# Etage0_ok_2.net
KiCad netlist of a schematic drawn in EAGLE
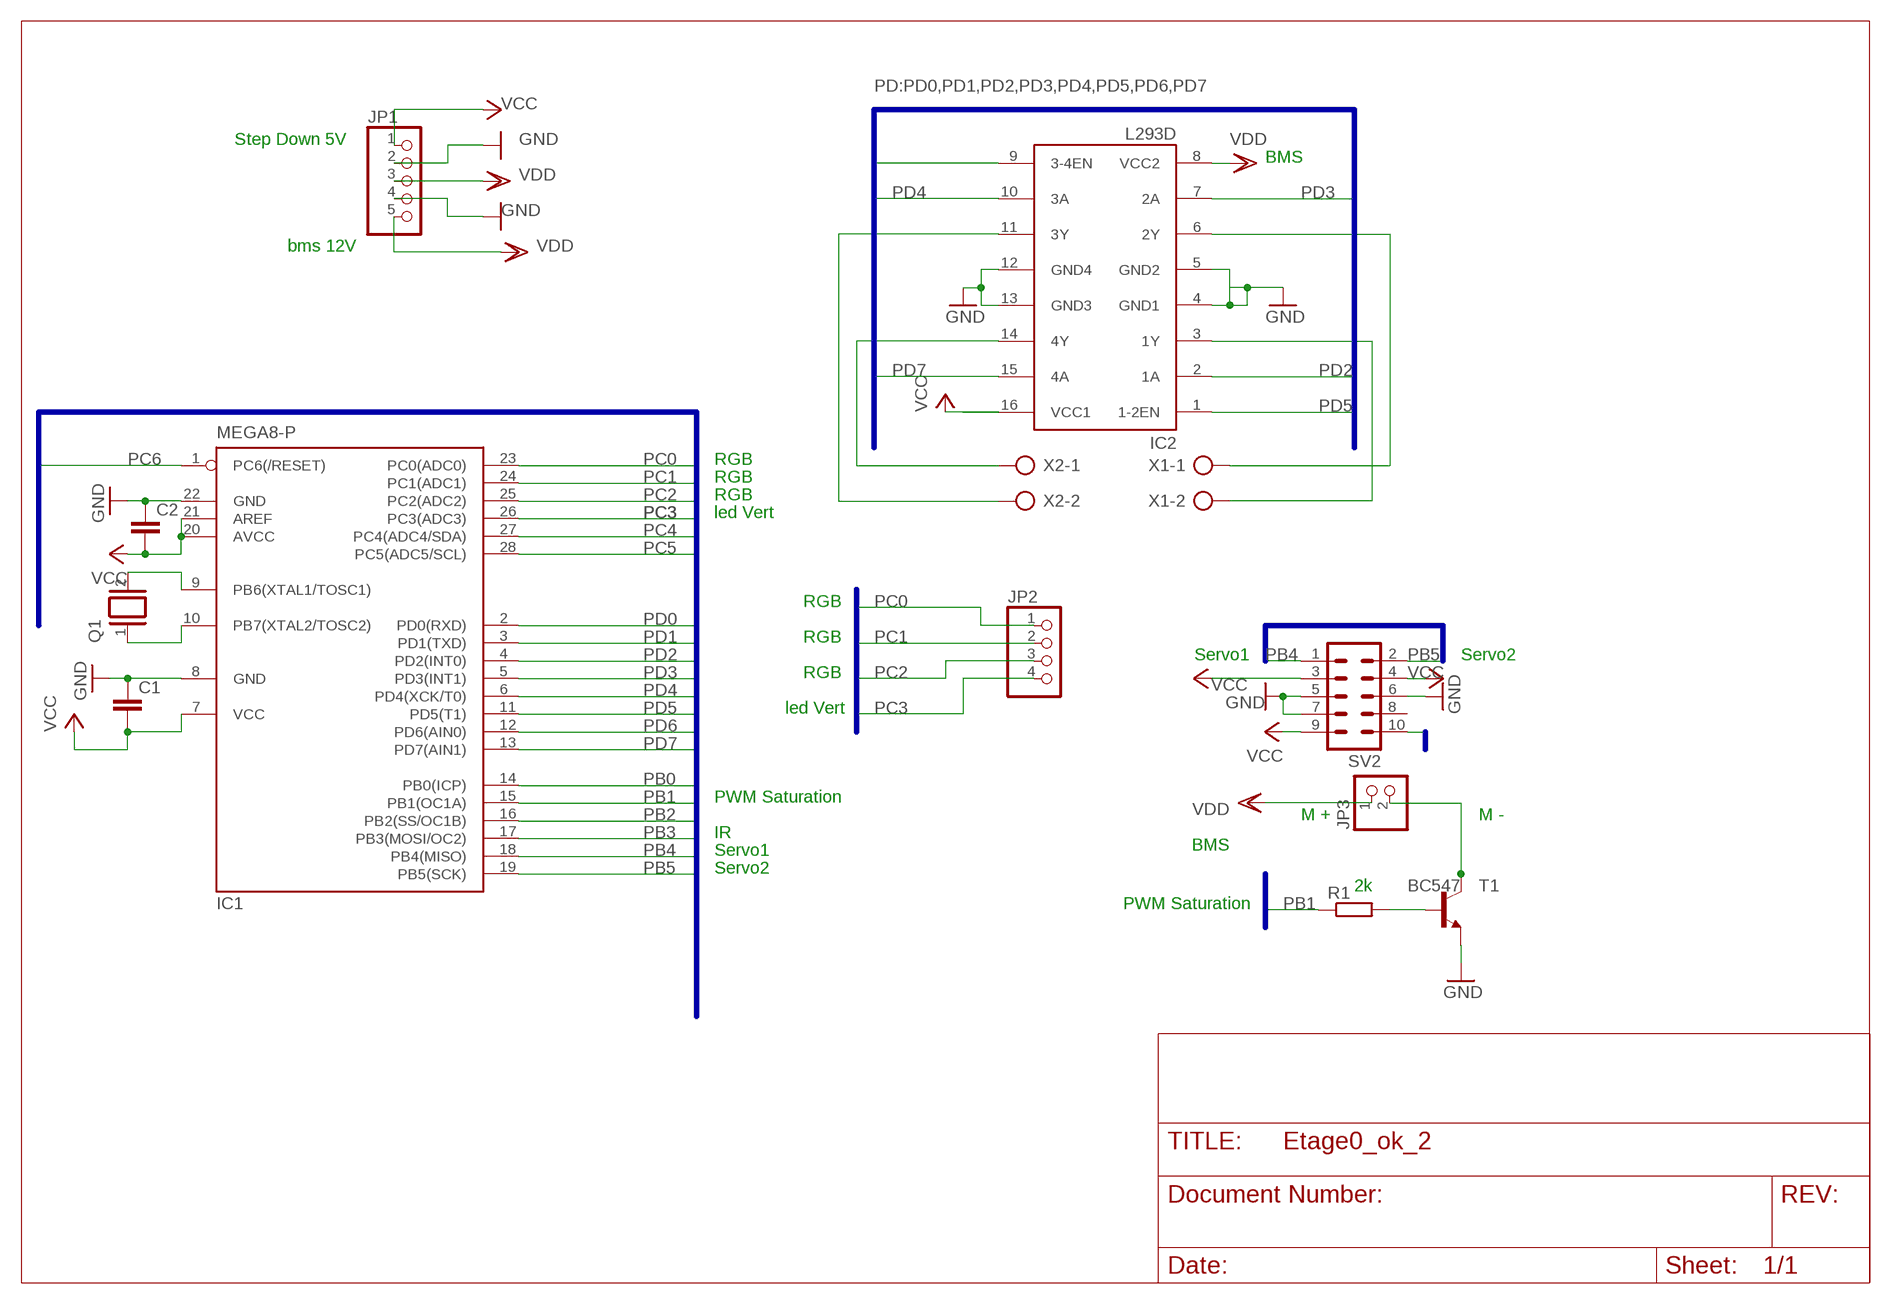
[diagram p0: schematic, sheet 1]

(export (version "E")
  (design (tool "Eeschema 10.0.6"))
  (components
    (comp (ref "C1")
      (value "C-EUC1206")
      (footprint "eagle-import:C1206")
      (libsource (lib "eagle-import") (part "C-EUC1206"))
    )
    (comp (ref "C2")
      (value "C-EUC1206")
      (footprint "eagle-import:C1206")
      (libsource (lib "eagle-import") (part "C-EUC1206"))
    )
    (comp (ref "IC1")
      (value "MEGA8-P")
      (footprint "eagle-import:DIL28-3")
      (libsource (lib "eagle-import") (part "MEGA8-P"))
    )
    (comp (ref "IC2")
      (value "L293D")
      (footprint "eagle-import:DIL16")
      (libsource (lib "eagle-import") (part "L293D"))
    )
    (comp (ref "JP1")
      (value "PINHD-1X5")
      (footprint "eagle-import:1X05")
      (libsource (lib "eagle-import") (part "PINHD-1X5"))
    )
    (comp (ref "JP2")
      (value "PINHD-1X4")
      (footprint "eagle-import:1X04")
      (libsource (lib "eagle-import") (part "PINHD-1X4"))
    )
    (comp (ref "JP3")
      (value "PINHD-1X2")
      (footprint "eagle-import:1X02")
      (libsource (lib "eagle-import") (part "PINHD-1X2"))
    )
    (comp (ref "Q1")
      (value "XTAL")
      (footprint "eagle-import:Q")
      (libsource (lib "eagle-import") (part "XTAL"))
    )
    (comp (ref "R1")
      (value "R-EU_0204/7")
      (footprint "eagle-import:0204_7")
      (libsource (lib "eagle-import") (part "R-EU_0204/7"))
    )
    (comp (ref "SV2")
      (value "MA05-2")
      (footprint "eagle-import:MA05-2")
      (libsource (lib "eagle-import") (part "MA05-2"))
    )
    (comp (ref "T1")
      (value "BC547")
      (footprint "eagle-import:TO92")
      (libsource (lib "eagle-import") (part "BC547"))
    )
    (comp (ref "X1")
      (value "AK300/2")
      (footprint "eagle-import:AK300_2")
      (libsource (lib "eagle-import") (part "AK300/2"))
    )
    (comp (ref "X2")
      (value "AK300/2")
      (footprint "eagle-import:AK300_2")
      (libsource (lib "eagle-import") (part "AK300/2"))
    )
  )
  (nets
    (net (code "2") (name "/PB0") (class "Default")
      (node (ref "IC1") (pin "14") (pinfunction "PB0(ICP)_14") (pintype "bidirectional"))
    )
    (net (code "3") (name "/PB1") (class "Default")
      (node (ref "IC1") (pin "15") (pinfunction "PB1(OC1A)_15") (pintype "bidirectional"))
      (node (ref "R1") (pin "1") (pinfunction "1_1") (pintype "passive"))
    )
    (net (code "4") (name "/PB2") (class "Default")
      (node (ref "IC1") (pin "16") (pinfunction "PB2(SS/OC1B)_16") (pintype "bidirectional"))
    )
    (net (code "5") (name "/PB3") (class "Default")
      (node (ref "IC1") (pin "17") (pinfunction "PB3(MOSI/OC2)_17") (pintype "bidirectional"))
      (node (ref "SV2") (pin "10") (pinfunction "10_10") (pintype "passive"))
    )
    (net (code "6") (name "/PB4") (class "Default")
      (node (ref "IC1") (pin "18") (pinfunction "PB4(MISO)_18") (pintype "bidirectional"))
      (node (ref "SV2") (pin "1") (pinfunction "1_1") (pintype "passive"))
    )
    (net (code "7") (name "/PB5") (class "Default")
      (node (ref "IC1") (pin "19") (pinfunction "PB5(SCK)_19") (pintype "bidirectional"))
      (node (ref "SV2") (pin "2") (pinfunction "2_2") (pintype "passive"))
    )
    (net (code "8") (name "/PC0") (class "Default")
      (node (ref "IC1") (pin "23") (pinfunction "PC0(ADC0)_23") (pintype "bidirectional"))
      (node (ref "JP2") (pin "1") (pinfunction "1_1") (pintype "passive"))
    )
    (net (code "9") (name "/PC1") (class "Default")
      (node (ref "IC1") (pin "24") (pinfunction "PC1(ADC1)_24") (pintype "bidirectional"))
      (node (ref "JP2") (pin "2") (pinfunction "2_2") (pintype "passive"))
    )
    (net (code "10") (name "/PC2") (class "Default")
      (node (ref "IC1") (pin "25") (pinfunction "PC2(ADC2)_25") (pintype "bidirectional"))
      (node (ref "JP2") (pin "3") (pinfunction "3_3") (pintype "passive"))
    )
    (net (code "11") (name "/PC3") (class "Default")
      (node (ref "IC1") (pin "26") (pinfunction "PC3(ADC3)_26") (pintype "bidirectional"))
      (node (ref "JP2") (pin "4") (pinfunction "4_4") (pintype "passive"))
    )
    (net (code "12") (name "/PC4") (class "Default")
      (node (ref "IC1") (pin "27") (pinfunction "PC4(ADC4/SDA)_27") (pintype "bidirectional"))
    )
    (net (code "13") (name "/PC5") (class "Default")
      (node (ref "IC1") (pin "28") (pinfunction "PC5(ADC5/SCL)_28") (pintype "bidirectional"))
    )
    (net (code "14") (name "/PC6") (class "Default")
      (node (ref "IC1") (pin "1") (pinfunction "PC6(/RESET)_1") (pintype "bidirectional"))
    )
    (net (code "15") (name "/PD0") (class "Default")
      (node (ref "IC1") (pin "2") (pinfunction "PD0(RXD)_2") (pintype "bidirectional"))
    )
    (net (code "16") (name "/PD1") (class "Default")
      (node (ref "IC1") (pin "3") (pinfunction "PD1(TXD)_3") (pintype "bidirectional"))
    )
    (net (code "17") (name "/PD2") (class "Default")
      (node (ref "IC1") (pin "4") (pinfunction "PD2(INT0)_4") (pintype "bidirectional"))
      (node (ref "IC2") (pin "2") (pinfunction "1A_2") (pintype "input"))
    )
    (net (code "18") (name "/PD3") (class "Default")
      (node (ref "IC1") (pin "5") (pinfunction "PD3(INT1)_5") (pintype "bidirectional"))
      (node (ref "IC2") (pin "7") (pinfunction "2A_7") (pintype "input"))
    )
    (net (code "19") (name "/PD4") (class "Default")
      (node (ref "IC1") (pin "6") (pinfunction "PD4(XCK/T0)_6") (pintype "bidirectional"))
      (node (ref "IC2") (pin "10") (pinfunction "3A_10") (pintype "input"))
    )
    (net (code "20") (name "/PD5") (class "Default")
      (node (ref "IC1") (pin "11") (pinfunction "PD5(T1)_11") (pintype "bidirectional"))
      (node (ref "IC2") (pin "1") (pinfunction "1-2EN_1") (pintype "input"))
    )
    (net (code "21") (name "/PD6") (class "Default")
      (node (ref "IC1") (pin "12") (pinfunction "PD6(AIN0)_12") (pintype "bidirectional"))
      (node (ref "IC2") (pin "9") (pinfunction "3-4EN_9") (pintype "input"))
    )
    (net (code "22") (name "/PD7") (class "Default")
      (node (ref "IC1") (pin "13") (pinfunction "PD7(AIN1)_13") (pintype "bidirectional"))
      (node (ref "IC2") (pin "15") (pinfunction "4A_15") (pintype "input"))
    )
    (net (code "24") (name "GND") (class "Default")
      (node (ref "C1") (pin "1") (pinfunction "1_1") (pintype "passive"))
      (node (ref "C2") (pin "1") (pinfunction "1_1") (pintype "passive"))
      (node (ref "IC1") (pin "22") (pinfunction "GND_22") (pintype "power_in"))
      (node (ref "IC1") (pin "8") (pinfunction "GND_8") (pintype "power_in"))
      (node (ref "IC2") (pin "12") (pinfunction "GND4_12") (pintype "power_in"))
      (node (ref "IC2") (pin "13") (pinfunction "GND3_13") (pintype "power_in"))
      (node (ref "IC2") (pin "4") (pinfunction "GND1_4") (pintype "power_in"))
      (node (ref "IC2") (pin "5") (pinfunction "GND2_5") (pintype "power_in"))
      (node (ref "JP1") (pin "2") (pinfunction "2_2") (pintype "passive"))
      (node (ref "JP1") (pin "4") (pinfunction "4_4") (pintype "passive"))
      (node (ref "SV2") (pin "5") (pinfunction "5_5") (pintype "passive"))
      (node (ref "SV2") (pin "6") (pinfunction "6_6") (pintype "passive"))
      (node (ref "SV2") (pin "7") (pinfunction "7_7") (pintype "passive"))
      (node (ref "T1") (pin "1") (pinfunction "E_1") (pintype "passive"))
    )
    (net (code "25") (name "Net-(IC1-PB6(XTAL1{slash}TOSC1))") (class "Default")
      (node (ref "IC1") (pin "9") (pinfunction "PB6(XTAL1/TOSC1)_9") (pintype "bidirectional"))
      (node (ref "Q1") (pin "2") (pinfunction "2_2") (pintype "passive"))
    )
    (net (code "26") (name "Net-(IC1-PB7(XTAL2{slash}TOSC2))") (class "Default")
      (node (ref "IC1") (pin "10") (pinfunction "PB7(XTAL2/TOSC2)_10") (pintype "bidirectional"))
      (node (ref "Q1") (pin "1") (pinfunction "1_1") (pintype "passive"))
    )
    (net (code "27") (name "Net-(IC2-1Y)") (class "Default")
      (node (ref "IC2") (pin "3") (pinfunction "1Y_3") (pintype "output"))
      (node (ref "X1") (pin "2") (pinfunction "KL_2") (pintype "passive"))
    )
    (net (code "28") (name "Net-(IC2-2Y)") (class "Default")
      (node (ref "IC2") (pin "6") (pinfunction "2Y_6") (pintype "output"))
      (node (ref "X1") (pin "1") (pinfunction "KL_1") (pintype "passive"))
    )
    (net (code "29") (name "Net-(IC2-3Y)") (class "Default")
      (node (ref "IC2") (pin "11") (pinfunction "3Y_11") (pintype "output"))
      (node (ref "X2") (pin "2") (pinfunction "KL_2") (pintype "passive"))
    )
    (net (code "30") (name "Net-(IC2-4Y)") (class "Default")
      (node (ref "IC2") (pin "14") (pinfunction "4Y_14") (pintype "output"))
      (node (ref "X2") (pin "1") (pinfunction "KL_1") (pintype "passive"))
    )
    (net (code "31") (name "Net-(T1-B)") (class "Default")
      (node (ref "R1") (pin "2") (pinfunction "2_2") (pintype "passive"))
      (node (ref "T1") (pin "2") (pinfunction "B_2") (pintype "passive"))
    )
    (net (code "32") (name "Net-(T1-C)") (class "Default")
      (node (ref "JP3") (pin "2") (pinfunction "2_2") (pintype "passive"))
      (node (ref "T1") (pin "3") (pinfunction "C_3") (pintype "passive"))
    )
    (net (code "33") (name "VCC") (class "Default")
      (node (ref "C1") (pin "2") (pinfunction "2_2") (pintype "passive"))
      (node (ref "C2") (pin "2") (pinfunction "2_2") (pintype "passive"))
      (node (ref "IC1") (pin "20") (pinfunction "AVCC_20") (pintype "power_in"))
      (node (ref "IC1") (pin "21") (pinfunction "AREF_21") (pintype "passive"))
      (node (ref "IC1") (pin "7") (pinfunction "VCC_7") (pintype "power_in"))
      (node (ref "IC2") (pin "16") (pinfunction "VCC1_16") (pintype "power_in"))
      (node (ref "JP1") (pin "1") (pinfunction "1_1") (pintype "passive"))
      (node (ref "SV2") (pin "3") (pinfunction "3_3") (pintype "passive"))
      (node (ref "SV2") (pin "4") (pinfunction "4_4") (pintype "passive"))
      (node (ref "SV2") (pin "9") (pinfunction "9_9") (pintype "passive"))
    )
    (net (code "34") (name "VDD") (class "Default")
      (node (ref "IC2") (pin "8") (pinfunction "VCC2_8") (pintype "power_in"))
      (node (ref "JP1") (pin "3") (pinfunction "3_3") (pintype "passive"))
      (node (ref "JP1") (pin "5") (pinfunction "5_5") (pintype "passive"))
      (node (ref "JP3") (pin "1") (pinfunction "1_1") (pintype "passive"))
    )
    (net (code "35") (name "unconnected-(SV2-Pad8)") (class "Default")
      (node (ref "SV2") (pin "8") (pinfunction "8_8") (pintype "passive"))
    )
  )
)
